# LVDS_Driver_Subsystem.net
KiCad netlist of a schematic drawn in Altium Designer
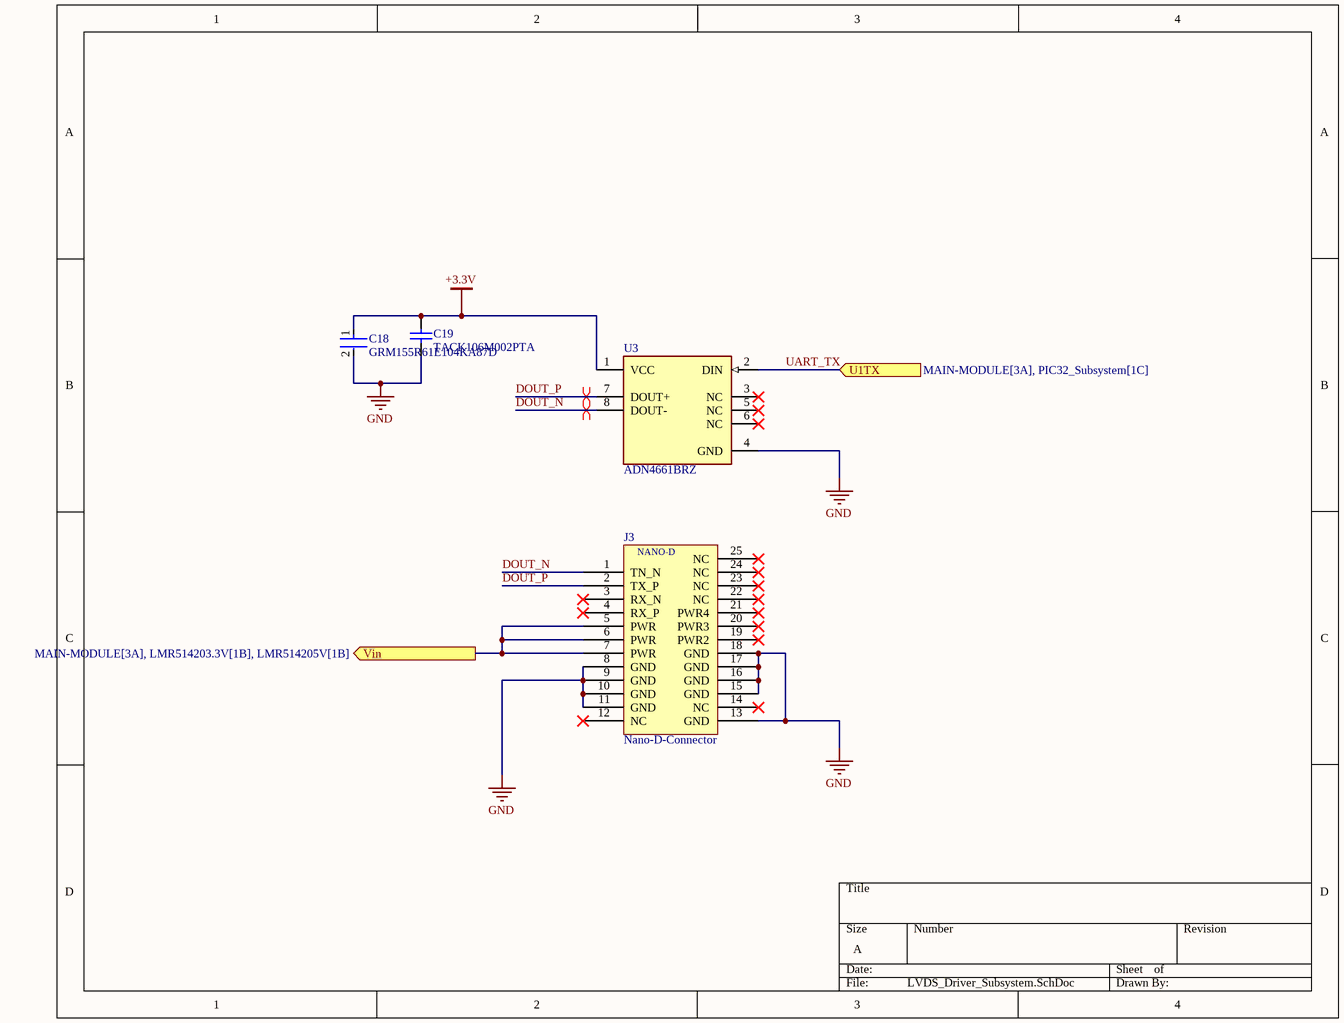
[diagram p0: LVDS_Driver_Subsystem.SchDoc]

(export (version "E")
  (design (tool "Eeschema 10.0.6"))
  (components
    (comp (ref "C18")
      (value "GRM155R61E104KA87D")
      (footprint "FP-GRM155-0_05-MFG")
      (description "CAP CER 0.1UF 25V X5R 0402")
      (fields (field (name "VOLTAGE") "25V") (field (name "TOLERANCE") "10%"))
      (libsource (lib "Altium Content Vault") (part "11868f565c42a9108669ba33697ecf6"))
    )
    (comp (ref "C19")
      (value "TACK106M002PTA")
      (footprint "CAPC1005X70X10NL20T00")
      (fields (field (name "MANUFACTURER") "AVX Interconnect / Elco"))
      (libsource (lib "Altium Content Vault") (part "CAP"))
    )
    (comp (ref "J3")
      (value "Nano-D-Connector")
      (footprint "A28400-025")
      (libsource (lib "Connectors") (part "Nano-D-Connector"))
    )
    (comp (ref "U3")
      (value "ADN4661BRZ")
      (footprint "FP-R-8-IPC_A")
      (description "IC DRIVER 1/0 8SOIC")
      (libsource (lib "Altium Content Vault") (part "f8d6ee1c26474eb5cd2f3fb550722cd"))
    )
  )
  (nets
    (net (code "1") (name "+3.3V") (class "Default")
      (node (ref "C18") (pin "1") (pinfunction "1_1") (pintype "passive"))
      (node (ref "C19") (pin "2") (pinfunction "2_2") (pintype "passive"))
      (node (ref "U3") (pin "1") (pinfunction "VCC_1") (pintype "power_in"))
    )
    (net (code "2") (name "/DOUT_N") (class "Default")
      (node (ref "J3") (pin "1") (pinfunction "TN_N_1") (pintype "passive"))
      (node (ref "U3") (pin "8") (pinfunction "DOUT-_8") (pintype "passive"))
    )
    (net (code "3") (name "/DOUT_P") (class "Default")
      (node (ref "J3") (pin "2") (pinfunction "TX_P_2") (pintype "passive"))
      (node (ref "U3") (pin "7") (pinfunction "DOUT+_7") (pintype "passive"))
    )
    (net (code "4") (name "/UART_TX") (class "Default")
      (node (ref "U3") (pin "2") (pinfunction "DIN_2") (pintype "input"))
    )
    (net (code "5") (name "/Vin") (class "Default")
      (node (ref "J3") (pin "5") (pinfunction "PWR_5") (pintype "passive"))
      (node (ref "J3") (pin "6") (pinfunction "PWR_6") (pintype "passive"))
      (node (ref "J3") (pin "7") (pinfunction "PWR_7") (pintype "passive"))
    )
    (net (code "6") (name "GND") (class "Default")
      (node (ref "C18") (pin "2") (pinfunction "2_2") (pintype "passive"))
      (node (ref "C19") (pin "1") (pinfunction "1_1") (pintype "passive"))
      (node (ref "J3") (pin "10") (pinfunction "GND_10") (pintype "passive"))
      (node (ref "J3") (pin "11") (pinfunction "GND_11") (pintype "passive"))
      (node (ref "J3") (pin "13") (pinfunction "GND_13") (pintype "passive"))
      (node (ref "J3") (pin "15") (pinfunction "GND_15") (pintype "passive"))
      (node (ref "J3") (pin "16") (pinfunction "GND_16") (pintype "passive"))
      (node (ref "J3") (pin "17") (pinfunction "GND_17") (pintype "passive"))
      (node (ref "J3") (pin "18") (pinfunction "GND_18") (pintype "passive"))
      (node (ref "J3") (pin "8") (pinfunction "GND_8") (pintype "passive"))
      (node (ref "J3") (pin "9") (pinfunction "GND_9") (pintype "passive"))
      (node (ref "U3") (pin "4") (pinfunction "GND_4") (pintype "power_in"))
    )
    (net (code "7") (name "unconnected-(J3-NC-Pad12)") (class "Default")
      (node (ref "J3") (pin "12") (pinfunction "NC_12") (pintype "passive+no_connect"))
    )
    (net (code "8") (name "unconnected-(J3-NC-Pad14)") (class "Default")
      (node (ref "J3") (pin "14") (pinfunction "NC_14") (pintype "passive+no_connect"))
    )
    (net (code "9") (name "unconnected-(J3-NC-Pad22)") (class "Default")
      (node (ref "J3") (pin "22") (pinfunction "NC_22") (pintype "passive+no_connect"))
    )
    (net (code "10") (name "unconnected-(J3-NC-Pad23)") (class "Default")
      (node (ref "J3") (pin "23") (pinfunction "NC_23") (pintype "passive+no_connect"))
    )
    (net (code "11") (name "unconnected-(J3-NC-Pad24)") (class "Default")
      (node (ref "J3") (pin "24") (pinfunction "NC_24") (pintype "passive+no_connect"))
    )
    (net (code "12") (name "unconnected-(J3-NC-Pad25)") (class "Default")
      (node (ref "J3") (pin "25") (pinfunction "NC_25") (pintype "passive+no_connect"))
    )
    (net (code "13") (name "unconnected-(J3-PWR2-Pad19)") (class "Default")
      (node (ref "J3") (pin "19") (pinfunction "PWR2_19") (pintype "passive+no_connect"))
    )
    (net (code "14") (name "unconnected-(J3-PWR3-Pad20)") (class "Default")
      (node (ref "J3") (pin "20") (pinfunction "PWR3_20") (pintype "passive+no_connect"))
    )
    (net (code "15") (name "unconnected-(J3-PWR4-Pad21)") (class "Default")
      (node (ref "J3") (pin "21") (pinfunction "PWR4_21") (pintype "passive+no_connect"))
    )
    (net (code "16") (name "unconnected-(J3-RX_N-Pad3)") (class "Default")
      (node (ref "J3") (pin "3") (pinfunction "RX_N_3") (pintype "passive+no_connect"))
    )
    (net (code "17") (name "unconnected-(J3-RX_P-Pad4)") (class "Default")
      (node (ref "J3") (pin "4") (pinfunction "RX_P_4") (pintype "passive+no_connect"))
    )
    (net (code "18") (name "unconnected-(U3-NC-Pad3)") (class "Default")
      (node (ref "U3") (pin "3") (pinfunction "NC_3") (pintype "passive+no_connect"))
    )
    (net (code "19") (name "unconnected-(U3-NC-Pad5)") (class "Default")
      (node (ref "U3") (pin "5") (pinfunction "NC_5") (pintype "passive+no_connect"))
    )
    (net (code "20") (name "unconnected-(U3-NC-Pad6)") (class "Default")
      (node (ref "U3") (pin "6") (pinfunction "NC_6") (pintype "passive+no_connect"))
    )
  )
)
